# Arduino_Neptune.net
KiCad netlist of a schematic drawn in EAGLE
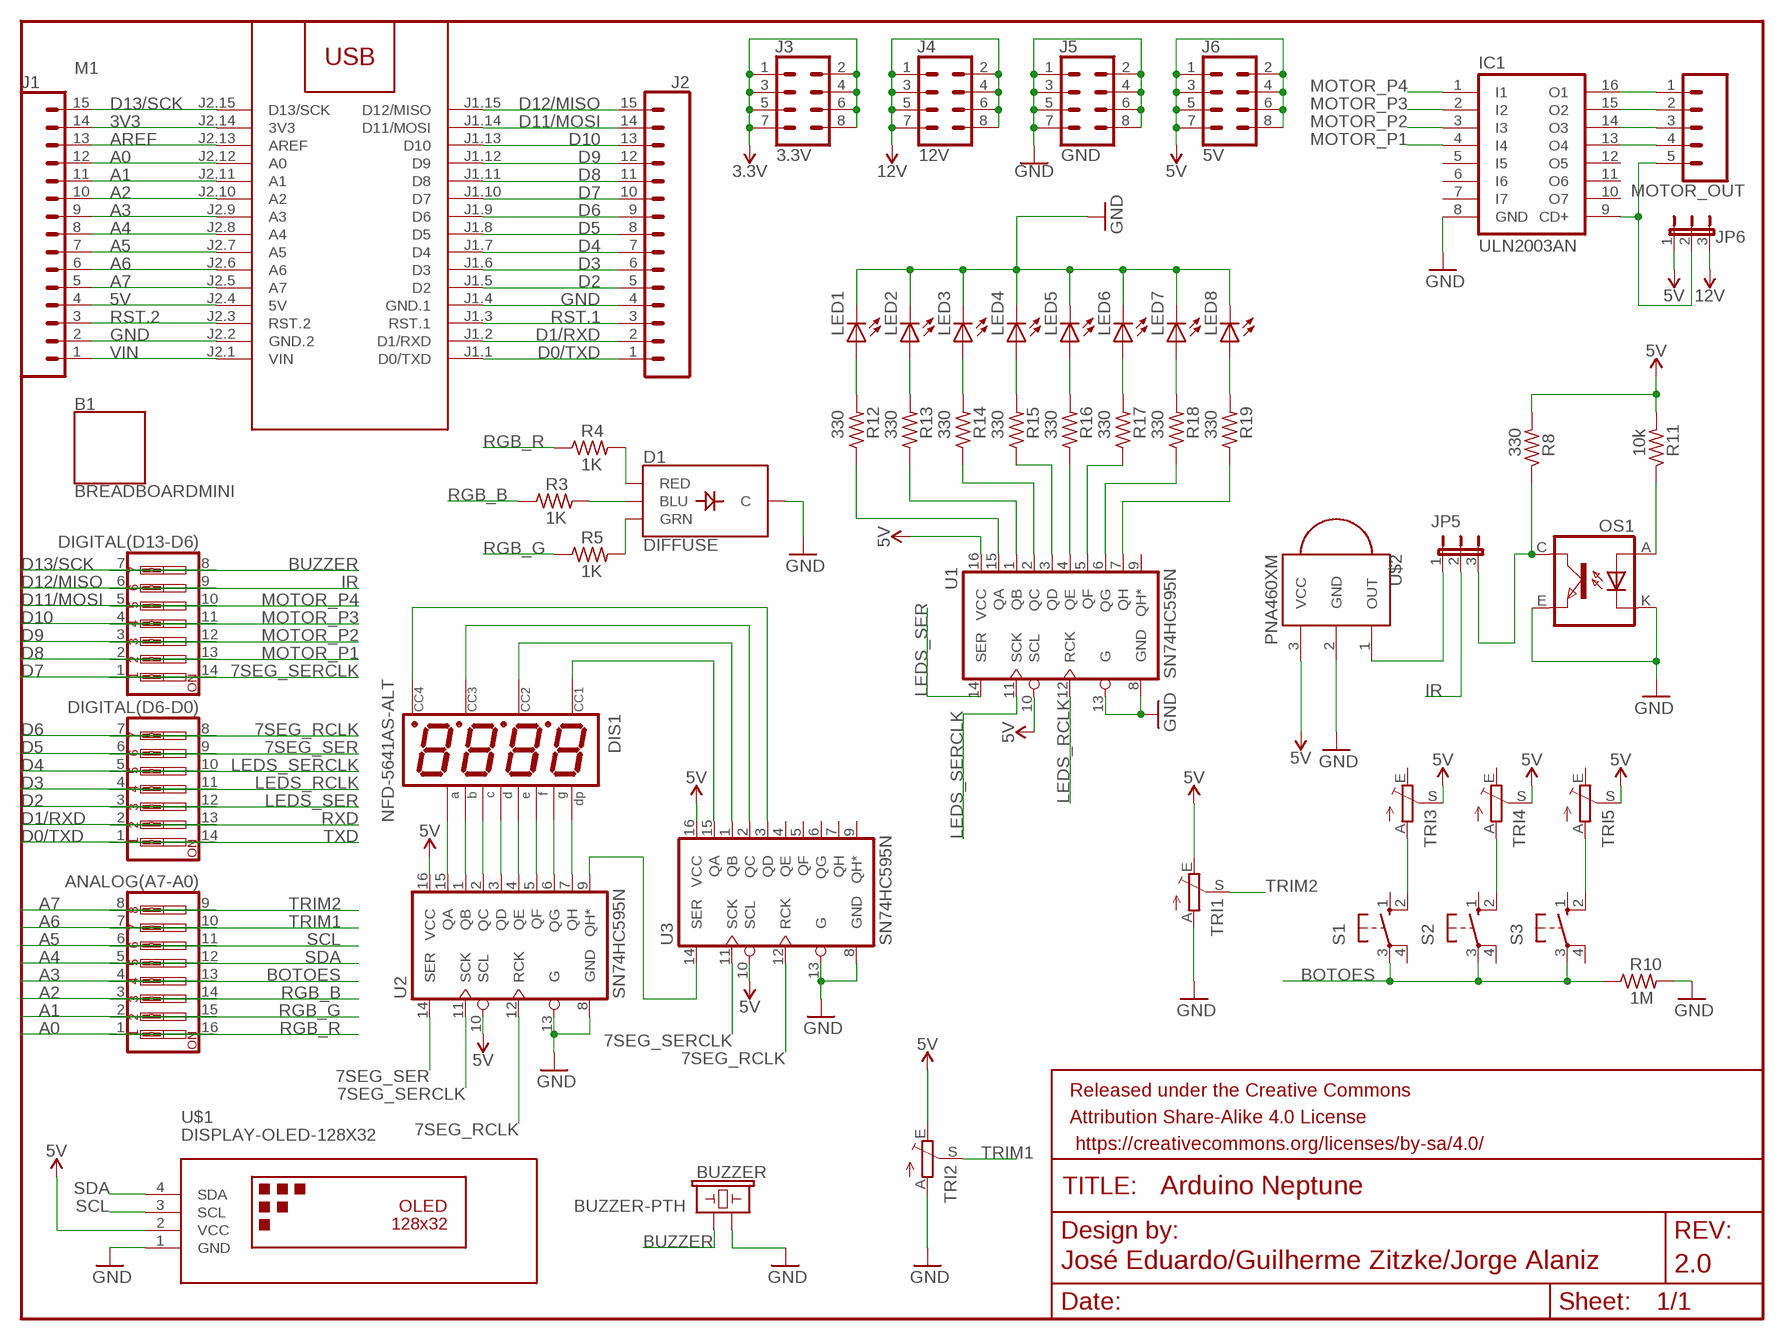
[diagram p0: schematic, sheet 1]

(export (version "E")
  (design (tool "Eeschema 10.0.6"))
  (components
    (comp (ref "ANALOG(A7-A0)")
      (value "SW_DIP-8")
      (footprint "eagle-import:EDG-08")
      (libsource (lib "eagle-import") (part "SW_DIP-8"))
    )
    (comp (ref "B1")
      (value "BREADBOARDMINI")
      (footprint "eagle-import:BREADBOARD-MINI")
      (libsource (lib "eagle-import") (part "BREADBOARDMINI"))
    )
    (comp (ref "BUZZER")
      (value "BUZZER-PTH")
      (footprint "eagle-import:BUZZER-12MM")
      (libsource (lib "eagle-import") (part "BUZZER-PTH"))
    )
    (comp (ref "D1")
      (value "DIFFUSE")
      (footprint "eagle-import:LED-RGB-THRU")
      (libsource (lib "eagle-import") (part "LED-RGB-CCDIFFUSE"))
    )
    (comp (ref "DIGITAL(D6-D0)")
      (value "SW_DIP-7")
      (footprint "eagle-import:EDG-07")
      (libsource (lib "eagle-import") (part "SW_DIP-7"))
    )
    (comp (ref "DIGITAL(D13-D6)")
      (value "SW_DIP-7")
      (footprint "eagle-import:EDG-07")
      (libsource (lib "eagle-import") (part "SW_DIP-7"))
    )
    (comp (ref "DIS1")
      (value "NFD-5641AS-ALT")
      (footprint "eagle-import:NFD-5641")
      (libsource (lib "eagle-import") (part "NFD-5641AS-ALT"))
    )
    (comp (ref "FRAME2")
      (value "FRAME-LETTER")
      (footprint "eagle-import:CREATIVE_COMMONS")
      (fields
        (field (name "DESIGNER") "José Eduardo/Guilherme Zitzke/Jorge Alaniz")
        (field (name "REV") "2.0")
      )
      (libsource (lib "eagle-import") (part "FRAME-LETTER"))
    )
    (comp (ref "IC1")
      (value "ULN2003AN")
      (footprint "eagle-import:DIL16")
      (libsource (lib "eagle-import") (part "ULN2003AN"))
    )
    (comp (ref "J1")
      (value "CONN_15LOCK_LONGPADS")
      (footprint "eagle-import:1X15_LOCK_LONGPADS")
      (libsource (lib "eagle-import") (part "CONN_15LOCK_LONGPADS"))
    )
    (comp (ref "J2")
      (value "CONN_15LOCK_LONGPADS")
      (footprint "eagle-import:1X15_LOCK_LONGPADS")
      (libsource (lib "eagle-import") (part "CONN_15LOCK_LONGPADS"))
    )
    (comp (ref "J3")
      (value "3.3V")
      (footprint "eagle-import:2X4")
      (libsource (lib "eagle-import") (part "CONN_04X2"))
    )
    (comp (ref "J4")
      (value "12V")
      (footprint "eagle-import:2X4")
      (libsource (lib "eagle-import") (part "CONN_04X2"))
    )
    (comp (ref "J5")
      (value "GND")
      (footprint "eagle-import:2X4")
      (libsource (lib "eagle-import") (part "CONN_04X2"))
    )
    (comp (ref "J6")
      (value "5V")
      (footprint "eagle-import:2X4")
      (libsource (lib "eagle-import") (part "CONN_04X2"))
    )
    (comp (ref "JP5")
      (value "JP2E")
      (footprint "eagle-import:JP2")
      (libsource (lib "eagle-import") (part "JP2E"))
    )
    (comp (ref "JP6")
      (value "JP2E")
      (footprint "eagle-import:JP2")
      (libsource (lib "eagle-import") (part "JP2E"))
    )
    (comp (ref "LED1")
      (value "LED5MM")
      (footprint "eagle-import:LED5MM")
      (libsource (lib "eagle-import") (part "LED5MM"))
    )
    (comp (ref "LED2")
      (value "LED5MM")
      (footprint "eagle-import:LED5MM")
      (libsource (lib "eagle-import") (part "LED5MM"))
    )
    (comp (ref "LED3")
      (value "LED5MM")
      (footprint "eagle-import:LED5MM")
      (libsource (lib "eagle-import") (part "LED5MM"))
    )
    (comp (ref "LED4")
      (value "LED5MM")
      (footprint "eagle-import:LED5MM")
      (libsource (lib "eagle-import") (part "LED5MM"))
    )
    (comp (ref "LED5")
      (value "LED5MM")
      (footprint "eagle-import:LED5MM")
      (libsource (lib "eagle-import") (part "LED5MM"))
    )
    (comp (ref "LED6")
      (value "LED5MM")
      (footprint "eagle-import:LED5MM")
      (libsource (lib "eagle-import") (part "LED5MM"))
    )
    (comp (ref "LED7")
      (value "LED5MM")
      (footprint "eagle-import:LED5MM")
      (libsource (lib "eagle-import") (part "LED5MM"))
    )
    (comp (ref "LED8")
      (value "LED5MM")
      (footprint "eagle-import:LED5MM")
      (libsource (lib "eagle-import") (part "LED5MM"))
    )
    (comp (ref "M1")
      (value "ARDUINO-NANO-3.0")
      (footprint "eagle-import:ARDUINO-NANO-3.0")
      (libsource (lib "eagle-import") (part "ARDUINO-NANO-3.0"))
    )
    (comp (ref "MOTOR_OUT")
      (value "CONN_05JST-VERT")
      (footprint "eagle-import:JST-5-PTH-VERT")
      (libsource (lib "eagle-import") (part "CONN_05JST-VERT"))
    )
    (comp (ref "OS1")
      (value "TCRT5000")
      (footprint "eagle-import:TCRT5000")
      (libsource (lib "eagle-import") (part "TCRT5000"))
    )
    (comp (ref "R3")
      (value "1K")
      (footprint "eagle-import:0204_7")
      (libsource (lib "eagle-import") (part "R-US_0204/7"))
    )
    (comp (ref "R4")
      (value "1K")
      (footprint "eagle-import:0204_7")
      (libsource (lib "eagle-import") (part "R-US_0204/7"))
    )
    (comp (ref "R5")
      (value "1K")
      (footprint "eagle-import:0204_7")
      (libsource (lib "eagle-import") (part "R-US_0204/7"))
    )
    (comp (ref "R8")
      (value "330")
      (footprint "eagle-import:0204_7")
      (libsource (lib "eagle-import") (part "R-US_0204/7"))
    )
    (comp (ref "R10")
      (value "1M")
      (footprint "eagle-import:0204_7")
      (libsource (lib "eagle-import") (part "R-US_0204/7"))
    )
    (comp (ref "R11")
      (value "10k")
      (footprint "eagle-import:0204_7")
      (libsource (lib "eagle-import") (part "R-US_0204/7"))
    )
    (comp (ref "R12")
      (value "330")
      (footprint "eagle-import:0204_7")
      (libsource (lib "eagle-import") (part "R-US_0204/7"))
    )
    (comp (ref "R13")
      (value "330")
      (footprint "eagle-import:0204_7")
      (libsource (lib "eagle-import") (part "R-US_0204/7"))
    )
    (comp (ref "R14")
      (value "330")
      (footprint "eagle-import:0204_7")
      (libsource (lib "eagle-import") (part "R-US_0204/7"))
    )
    (comp (ref "R15")
      (value "330")
      (footprint "eagle-import:0204_7")
      (libsource (lib "eagle-import") (part "R-US_0204/7"))
    )
    (comp (ref "R16")
      (value "330")
      (footprint "eagle-import:0204_7")
      (libsource (lib "eagle-import") (part "R-US_0204/7"))
    )
    (comp (ref "R17")
      (value "330")
      (footprint "eagle-import:0204_7")
      (libsource (lib "eagle-import") (part "R-US_0204/7"))
    )
    (comp (ref "R18")
      (value "330")
      (footprint "eagle-import:0204_7")
      (libsource (lib "eagle-import") (part "R-US_0204/7"))
    )
    (comp (ref "R19")
      (value "330")
      (footprint "eagle-import:0204_7")
      (libsource (lib "eagle-import") (part "R-US_0204/7"))
    )
    (comp (ref "S1")
      (value "40-XX")
      (footprint "eagle-import:B3F-40XX")
      (fields (field (name "MF") "OMRON COMPONENTS USA") (field (name "MPN") "B3F-4000"))
      (libsource (lib "eagle-import") (part "40-XX"))
    )
    (comp (ref "S2")
      (value "40-XX")
      (footprint "eagle-import:B3F-40XX")
      (fields (field (name "MF") "OMRON COMPONENTS USA") (field (name "MPN") "B3F-4000"))
      (libsource (lib "eagle-import") (part "40-XX"))
    )
    (comp (ref "S3")
      (value "40-XX")
      (footprint "eagle-import:B3F-40XX")
      (fields (field (name "MF") "OMRON COMPONENTS USA") (field (name "MPN") "B3F-4000"))
      (libsource (lib "eagle-import") (part "40-XX"))
    )
    (comp (ref "TRI1")
      (value "TRIM_EU-B64Y")
      (footprint "eagle-import:B64Y")
      (libsource (lib "eagle-import") (part "TRIM_EU-B64Y"))
    )
    (comp (ref "TRI2")
      (value "TRIM_EU-B64Y")
      (footprint "eagle-import:B64Y")
      (libsource (lib "eagle-import") (part "TRIM_EU-B64Y"))
    )
    (comp (ref "TRI3")
      (value "TRIM_EU-B64Y")
      (footprint "eagle-import:B64Y")
      (libsource (lib "eagle-import") (part "TRIM_EU-B64Y"))
    )
    (comp (ref "TRI4")
      (value "TRIM_EU-B64Y")
      (footprint "eagle-import:B64Y")
      (libsource (lib "eagle-import") (part "TRIM_EU-B64Y"))
    )
    (comp (ref "TRI5")
      (value "TRIM_EU-B64Y")
      (footprint "eagle-import:B64Y")
      (libsource (lib "eagle-import") (part "TRIM_EU-B64Y"))
    )
    (comp (ref "U$1")
      (value "DISPLAY-OLED-128X32")
      (footprint "eagle-import:DISPLAY-OLED-128X32")
      (libsource (lib "eagle-import") (part "DISPLAY-OLED-128X32"))
    )
    (comp (ref "U$2")
      (value "PNA460XM")
      (footprint "eagle-import:PNA460XM")
      (libsource (lib "eagle-import") (part "PNA460XM"))
    )
    (comp (ref "U1")
      (value "SN74HC595N")
      (footprint "eagle-import:DIP16")
      (libsource (lib "eagle-import") (part "74595NHC"))
    )
    (comp (ref "U2")
      (value "SN74HC595N")
      (footprint "eagle-import:DIP16")
      (libsource (lib "eagle-import") (part "74595NHC"))
    )
    (comp (ref "U3")
      (value "SN74HC595N")
      (footprint "eagle-import:DIP16")
      (libsource (lib "eagle-import") (part "74595NHC"))
    )
  )
  (nets
    (net (code "1") (name "/3V3") (class "Default")
      (node (ref "J1") (pin "14") (pinfunction "14_14") (pintype "passive"))
      (node (ref "M1") (pin "J2.14") (pinfunction "3V3_J2.14") (pintype "power_in"))
    )
    (net (code "2") (name "/7SEG_RCLK") (class "Default")
      (node (ref "DIGITAL(D6-D0)") (pin "7") (pinfunction "7_7") (pintype "passive"))
      (node (ref "U2") (pin "12") (pinfunction "RCK_12") (pintype "input"))
      (node (ref "U3") (pin "12") (pinfunction "RCK_12") (pintype "input"))
    )
    (net (code "3") (name "/7SEG_SER") (class "Default")
      (node (ref "DIGITAL(D6-D0)") (pin "6") (pinfunction "6_6") (pintype "passive"))
      (node (ref "U2") (pin "14") (pinfunction "SER_14") (pintype "input"))
    )
    (net (code "4") (name "/7SEG_SERCLK") (class "Default")
      (node (ref "DIGITAL(D13-D6)") (pin "1") (pinfunction "1_1") (pintype "passive"))
      (node (ref "U2") (pin "11") (pinfunction "SCK_11") (pintype "input"))
      (node (ref "U3") (pin "11") (pinfunction "SCK_11") (pintype "input"))
    )
    (net (code "5") (name "/A0") (class "Default")
      (node (ref "ANALOG(A7-A0)") (pin "16") (pinfunction "16_16") (pintype "passive"))
      (node (ref "J1") (pin "12") (pinfunction "12_12") (pintype "passive"))
      (node (ref "M1") (pin "J2.12") (pinfunction "A0_J2.12") (pintype "bidirectional"))
    )
    (net (code "6") (name "/A1") (class "Default")
      (node (ref "ANALOG(A7-A0)") (pin "15") (pinfunction "15_15") (pintype "passive"))
      (node (ref "J1") (pin "11") (pinfunction "11_11") (pintype "passive"))
      (node (ref "M1") (pin "J2.11") (pinfunction "A1_J2.11") (pintype "bidirectional"))
    )
    (net (code "7") (name "/A2") (class "Default")
      (node (ref "ANALOG(A7-A0)") (pin "14") (pinfunction "14_14") (pintype "passive"))
      (node (ref "J1") (pin "10") (pinfunction "10_10") (pintype "passive"))
      (node (ref "M1") (pin "J2.10") (pinfunction "A2_J2.10") (pintype "bidirectional"))
    )
    (net (code "8") (name "/A3") (class "Default")
      (node (ref "ANALOG(A7-A0)") (pin "13") (pinfunction "13_13") (pintype "passive"))
      (node (ref "J1") (pin "9") (pinfunction "9_9") (pintype "passive"))
      (node (ref "M1") (pin "J2.9") (pinfunction "A3_J2.9") (pintype "bidirectional"))
    )
    (net (code "9") (name "/A4") (class "Default")
      (node (ref "ANALOG(A7-A0)") (pin "12") (pinfunction "12_12") (pintype "passive"))
      (node (ref "J1") (pin "8") (pinfunction "8_8") (pintype "passive"))
      (node (ref "M1") (pin "J2.8") (pinfunction "A4_J2.8") (pintype "bidirectional"))
    )
    (net (code "10") (name "/A5") (class "Default")
      (node (ref "ANALOG(A7-A0)") (pin "11") (pinfunction "11_11") (pintype "passive"))
      (node (ref "J1") (pin "7") (pinfunction "7_7") (pintype "passive"))
      (node (ref "M1") (pin "J2.7") (pinfunction "A5_J2.7") (pintype "bidirectional"))
    )
    (net (code "11") (name "/A6") (class "Default")
      (node (ref "ANALOG(A7-A0)") (pin "10") (pinfunction "10_10") (pintype "passive"))
      (node (ref "J1") (pin "6") (pinfunction "6_6") (pintype "passive"))
      (node (ref "M1") (pin "J2.6") (pinfunction "A6_J2.6") (pintype "bidirectional"))
    )
    (net (code "12") (name "/A7") (class "Default")
      (node (ref "ANALOG(A7-A0)") (pin "9") (pinfunction "9_9") (pintype "passive"))
      (node (ref "J1") (pin "5") (pinfunction "5_5") (pintype "passive"))
      (node (ref "M1") (pin "J2.5") (pinfunction "A7_J2.5") (pintype "bidirectional"))
    )
    (net (code "13") (name "/AREF") (class "Default")
      (node (ref "J1") (pin "13") (pinfunction "13_13") (pintype "passive"))
      (node (ref "M1") (pin "J2.13") (pinfunction "AREF_J2.13") (pintype "bidirectional"))
    )
    (net (code "14") (name "/BOTOES") (class "Default")
      (node (ref "ANALOG(A7-A0)") (pin "4") (pinfunction "4_4") (pintype "passive"))
      (node (ref "R10") (pin "1") (pinfunction "1_1") (pintype "passive"))
      (node (ref "S1") (pin "3") (pinfunction "P_3") (pintype "passive"))
      (node (ref "S2") (pin "3") (pinfunction "P_3") (pintype "passive"))
      (node (ref "S3") (pin "3") (pinfunction "P_3") (pintype "passive"))
    )
    (net (code "15") (name "/BUZZER") (class "Default")
      (node (ref "BUZZER") (pin "+") (pinfunction "1_+") (pintype "passive"))
      (node (ref "DIGITAL(D13-D6)") (pin "7") (pinfunction "7_7") (pintype "passive"))
    )
    (net (code "16") (name "/D0{slash}TXD") (class "Default")
      (node (ref "DIGITAL(D6-D0)") (pin "14") (pinfunction "14_14") (pintype "passive"))
      (node (ref "J2") (pin "1") (pinfunction "1_1") (pintype "passive"))
      (node (ref "M1") (pin "J1.1") (pinfunction "D0/TXD_J1.1") (pintype "bidirectional"))
    )
    (net (code "17") (name "/D1{slash}RXD") (class "Default")
      (node (ref "DIGITAL(D6-D0)") (pin "13") (pinfunction "13_13") (pintype "passive"))
      (node (ref "J2") (pin "2") (pinfunction "2_2") (pintype "passive"))
      (node (ref "M1") (pin "J1.2") (pinfunction "D1/RXD_J1.2") (pintype "bidirectional"))
    )
    (net (code "18") (name "/D2") (class "Default")
      (node (ref "DIGITAL(D6-D0)") (pin "12") (pinfunction "12_12") (pintype "passive"))
      (node (ref "J2") (pin "5") (pinfunction "5_5") (pintype "passive"))
      (node (ref "M1") (pin "J1.5") (pinfunction "D2_J1.5") (pintype "bidirectional"))
    )
    (net (code "19") (name "/D3") (class "Default")
      (node (ref "DIGITAL(D6-D0)") (pin "11") (pinfunction "11_11") (pintype "passive"))
      (node (ref "J2") (pin "6") (pinfunction "6_6") (pintype "passive"))
      (node (ref "M1") (pin "J1.6") (pinfunction "D3_J1.6") (pintype "bidirectional"))
    )
    (net (code "20") (name "/D4") (class "Default")
      (node (ref "DIGITAL(D6-D0)") (pin "10") (pinfunction "10_10") (pintype "passive"))
      (node (ref "J2") (pin "7") (pinfunction "7_7") (pintype "passive"))
      (node (ref "M1") (pin "J1.7") (pinfunction "D4_J1.7") (pintype "bidirectional"))
    )
    (net (code "21") (name "/D5") (class "Default")
      (node (ref "DIGITAL(D6-D0)") (pin "9") (pinfunction "9_9") (pintype "passive"))
      (node (ref "J2") (pin "8") (pinfunction "8_8") (pintype "passive"))
      (node (ref "M1") (pin "J1.8") (pinfunction "D5_J1.8") (pintype "bidirectional"))
    )
    (net (code "22") (name "/D6") (class "Default")
      (node (ref "DIGITAL(D6-D0)") (pin "8") (pinfunction "8_8") (pintype "passive"))
      (node (ref "J2") (pin "9") (pinfunction "9_9") (pintype "passive"))
      (node (ref "M1") (pin "J1.9") (pinfunction "D6_J1.9") (pintype "bidirectional"))
    )
    (net (code "23") (name "/D7") (class "Default")
      (node (ref "DIGITAL(D13-D6)") (pin "14") (pinfunction "14_14") (pintype "passive"))
      (node (ref "J2") (pin "10") (pinfunction "10_10") (pintype "passive"))
      (node (ref "M1") (pin "J1.10") (pinfunction "D7_J1.10") (pintype "bidirectional"))
    )
    (net (code "24") (name "/D8") (class "Default")
      (node (ref "DIGITAL(D13-D6)") (pin "13") (pinfunction "13_13") (pintype "passive"))
      (node (ref "J2") (pin "11") (pinfunction "11_11") (pintype "passive"))
      (node (ref "M1") (pin "J1.11") (pinfunction "D8_J1.11") (pintype "bidirectional"))
    )
    (net (code "25") (name "/D9") (class "Default")
      (node (ref "DIGITAL(D13-D6)") (pin "12") (pinfunction "12_12") (pintype "passive"))
      (node (ref "J2") (pin "12") (pinfunction "12_12") (pintype "passive"))
      (node (ref "M1") (pin "J1.12") (pinfunction "D9_J1.12") (pintype "bidirectional"))
    )
    (net (code "26") (name "/D10") (class "Default")
      (node (ref "DIGITAL(D13-D6)") (pin "11") (pinfunction "11_11") (pintype "passive"))
      (node (ref "J2") (pin "13") (pinfunction "13_13") (pintype "passive"))
      (node (ref "M1") (pin "J1.13") (pinfunction "D10_J1.13") (pintype "bidirectional"))
    )
    (net (code "27") (name "/D11{slash}MOSI") (class "Default")
      (node (ref "DIGITAL(D13-D6)") (pin "10") (pinfunction "10_10") (pintype "passive"))
      (node (ref "J2") (pin "14") (pinfunction "14_14") (pintype "passive"))
      (node (ref "M1") (pin "J1.14") (pinfunction "D11/MOSI_J1.14") (pintype "bidirectional"))
    )
    (net (code "28") (name "/D12{slash}MISO") (class "Default")
      (node (ref "DIGITAL(D13-D6)") (pin "9") (pinfunction "9_9") (pintype "passive"))
      (node (ref "J2") (pin "15") (pinfunction "15_15") (pintype "passive"))
      (node (ref "M1") (pin "J1.15") (pinfunction "D12/MISO_J1.15") (pintype "bidirectional"))
    )
    (net (code "29") (name "/D13{slash}SCK") (class "Default")
      (node (ref "DIGITAL(D13-D6)") (pin "8") (pinfunction "8_8") (pintype "passive"))
      (node (ref "J1") (pin "15") (pinfunction "15_15") (pintype "passive"))
      (node (ref "M1") (pin "J2.15") (pinfunction "D13/SCK_J2.15") (pintype "bidirectional"))
    )
    (net (code "30") (name "/IR") (class "Default")
      (node (ref "DIGITAL(D13-D6)") (pin "6") (pinfunction "6_6") (pintype "passive"))
      (node (ref "JP5") (pin "2") (pinfunction "2_2") (pintype "passive"))
    )
    (net (code "31") (name "/LEDS_RCLK") (class "Default")
      (node (ref "DIGITAL(D6-D0)") (pin "4") (pinfunction "4_4") (pintype "passive"))
      (node (ref "U1") (pin "12") (pinfunction "RCK_12") (pintype "input"))
    )
    (net (code "32") (name "/LEDS_SER") (class "Default")
      (node (ref "DIGITAL(D6-D0)") (pin "3") (pinfunction "3_3") (pintype "passive"))
      (node (ref "U1") (pin "14") (pinfunction "SER_14") (pintype "input"))
    )
    (net (code "33") (name "/LEDS_SERCLK") (class "Default")
      (node (ref "DIGITAL(D6-D0)") (pin "5") (pinfunction "5_5") (pintype "passive"))
      (node (ref "U1") (pin "11") (pinfunction "SCK_11") (pintype "input"))
    )
    (net (code "34") (name "/MOTOR_P1") (class "Default")
      (node (ref "DIGITAL(D13-D6)") (pin "2") (pinfunction "2_2") (pintype "passive"))
      (node (ref "IC1") (pin "4") (pinfunction "I4_4") (pintype "input"))
    )
    (net (code "35") (name "/MOTOR_P2") (class "Default")
      (node (ref "DIGITAL(D13-D6)") (pin "3") (pinfunction "3_3") (pintype "passive"))
      (node (ref "IC1") (pin "3") (pinfunction "I3_3") (pintype "input"))
    )
    (net (code "36") (name "/MOTOR_P3") (class "Default")
      (node (ref "DIGITAL(D13-D6)") (pin "4") (pinfunction "4_4") (pintype "passive"))
      (node (ref "IC1") (pin "2") (pinfunction "I2_2") (pintype "input"))
    )
    (net (code "37") (name "/MOTOR_P4") (class "Default")
      (node (ref "DIGITAL(D13-D6)") (pin "5") (pinfunction "5_5") (pintype "passive"))
      (node (ref "IC1") (pin "1") (pinfunction "I1_1") (pintype "input"))
    )
    (net (code "38") (name "/RGB_B") (class "Default")
      (node (ref "ANALOG(A7-A0)") (pin "3") (pinfunction "3_3") (pintype "passive"))
      (node (ref "R3") (pin "1") (pinfunction "1_1") (pintype "passive"))
    )
    (net (code "39") (name "/RGB_G") (class "Default")
      (node (ref "ANALOG(A7-A0)") (pin "2") (pinfunction "2_2") (pintype "passive"))
      (node (ref "R5") (pin "1") (pinfunction "1_1") (pintype "passive"))
    )
    (net (code "40") (name "/RGB_R") (class "Default")
      (node (ref "ANALOG(A7-A0)") (pin "1") (pinfunction "1_1") (pintype "passive"))
      (node (ref "R4") (pin "1") (pinfunction "1_1") (pintype "passive"))
    )
    (net (code "41") (name "/RST.1") (class "Default")
      (node (ref "J2") (pin "3") (pinfunction "3_3") (pintype "passive"))
      (node (ref "M1") (pin "J1.3") (pinfunction "RST.1_J1.3") (pintype "bidirectional"))
    )
    (net (code "42") (name "/RST.2") (class "Default")
      (node (ref "J1") (pin "3") (pinfunction "3_3") (pintype "passive"))
      (node (ref "M1") (pin "J2.3") (pinfunction "RST.2_J2.3") (pintype "bidirectional"))
    )
    (net (code "43") (name "/RXD") (class "Default")
      (node (ref "DIGITAL(D6-D0)") (pin "2") (pinfunction "2_2") (pintype "passive"))
    )
    (net (code "44") (name "/SCL") (class "Default")
      (node (ref "ANALOG(A7-A0)") (pin "6") (pinfunction "6_6") (pintype "passive"))
      (node (ref "U$1") (pin "3") (pinfunction "SCL_3") (pintype "bidirectional"))
    )
    (net (code "45") (name "/SDA") (class "Default")
      (node (ref "ANALOG(A7-A0)") (pin "5") (pinfunction "5_5") (pintype "passive"))
      (node (ref "U$1") (pin "4") (pinfunction "SDA_4") (pintype "bidirectional"))
    )
    (net (code "46") (name "/TRIM1") (class "Default")
      (node (ref "ANALOG(A7-A0)") (pin "7") (pinfunction "7_7") (pintype "passive"))
      (node (ref "TRI2") (pin "S") (pinfunction "S_S") (pintype "passive"))
    )
    (net (code "47") (name "/TRIM2") (class "Default")
      (node (ref "ANALOG(A7-A0)") (pin "8") (pinfunction "8_8") (pintype "passive"))
      (node (ref "TRI1") (pin "S") (pinfunction "S_S") (pintype "passive"))
    )
    (net (code "48") (name "/TXD") (class "Default")
      (node (ref "DIGITAL(D6-D0)") (pin "1") (pinfunction "1_1") (pintype "passive"))
    )
    (net (code "49") (name "/VIN") (class "Default")
      (node (ref "J1") (pin "1") (pinfunction "1_1") (pintype "passive"))
      (node (ref "M1") (pin "J2.1") (pinfunction "VIN_J2.1") (pintype "power_in"))
    )
    (net (code "50") (name "3.3V") (class "Default")
      (node (ref "J3") (pin "1") (pinfunction "1_1") (pintype "passive"))
      (node (ref "J3") (pin "2") (pinfunction "2_2") (pintype "passive"))
      (node (ref "J3") (pin "3") (pinfunction "3_3") (pintype "passive"))
      (node (ref "J3") (pin "4") (pinfunction "4_4") (pintype "passive"))
      (node (ref "J3") (pin "5") (pinfunction "5_5") (pintype "passive"))
      (node (ref "J3") (pin "6") (pinfunction "6_6") (pintype "passive"))
      (node (ref "J3") (pin "7") (pinfunction "7_7") (pintype "passive"))
      (node (ref "J3") (pin "8") (pinfunction "8_8") (pintype "passive"))
    )
    (net (code "51") (name "5V") (class "Default")
      (node (ref "J1") (pin "4") (pinfunction "4_4") (pintype "passive"))
      (node (ref "J6") (pin "1") (pinfunction "1_1") (pintype "passive"))
      (node (ref "J6") (pin "2") (pinfunction "2_2") (pintype "passive"))
      (node (ref "J6") (pin "3") (pinfunction "3_3") (pintype "passive"))
      (node (ref "J6") (pin "4") (pinfunction "4_4") (pintype "passive"))
      (node (ref "J6") (pin "5") (pinfunction "5_5") (pintype "passive"))
      (node (ref "J6") (pin "6") (pinfunction "6_6") (pintype "passive"))
      (node (ref "J6") (pin "7") (pinfunction "7_7") (pintype "passive"))
      (node (ref "J6") (pin "8") (pinfunction "8_8") (pintype "passive"))
      (node (ref "JP6") (pin "1") (pinfunction "1_1") (pintype "passive"))
      (node (ref "M1") (pin "J2.4") (pinfunction "5V_J2.4") (pintype "power_in"))
      (node (ref "R11") (pin "2") (pinfunction "2_2") (pintype "passive"))
      (node (ref "R8") (pin "2") (pinfunction "2_2") (pintype "passive"))
      (node (ref "TRI1") (pin "E") (pinfunction "E_E") (pintype "passive"))
      (node (ref "TRI2") (pin "E") (pinfunction "E_E") (pintype "passive"))
      (node (ref "TRI3") (pin "S") (pinfunction "S_S") (pintype "passive"))
      (node (ref "TRI4") (pin "S") (pinfunction "S_S") (pintype "passive"))
      (node (ref "TRI5") (pin "S") (pinfunction "S_S") (pintype "passive"))
      (node (ref "U$1") (pin "2") (pinfunction "VCC_2") (pintype "power_in"))
      (node (ref "U$2") (pin "3") (pinfunction "VCC_3") (pintype "power_in"))
      (node (ref "U1") (pin "10") (pinfunction "SCL_10") (pintype "input"))
      (node (ref "U1") (pin "16") (pinfunction "VCC_16") (pintype "power_in"))
      (node (ref "U2") (pin "10") (pinfunction "SCL_10") (pintype "input"))
      (node (ref "U2") (pin "16") (pinfunction "VCC_16") (pintype "power_in"))
      (node (ref "U3") (pin "10") (pinfunction "SCL_10") (pintype "input"))
      (node (ref "U3") (pin "16") (pinfunction "VCC_16") (pintype "power_in"))
    )
    (net (code "52") (name "12V") (class "Default")
      (node (ref "J4") (pin "1") (pinfunction "1_1") (pintype "passive"))
      (node (ref "J4") (pin "2") (pinfunction "2_2") (pintype "passive"))
      (node (ref "J4") (pin "3") (pinfunction "3_3") (pintype "passive"))
      (node (ref "J4") (pin "4") (pinfunction "4_4") (pintype "passive"))
      (node (ref "J4") (pin "5") (pinfunction "5_5") (pintype "passive"))
      (node (ref "J4") (pin "6") (pinfunction "6_6") (pintype "passive"))
      (node (ref "J4") (pin "7") (pinfunction "7_7") (pintype "passive"))
      (node (ref "J4") (pin "8") (pinfunction "8_8") (pintype "passive"))
      (node (ref "JP6") (pin "3") (pinfunction "3_3") (pintype "passive"))
    )
    (net (code "53") (name "GND") (class "Default")
      (node (ref "BUZZER") (pin "-") (pinfunction "2_-") (pintype "passive"))
      (node (ref "D1") (pin "2") (pinfunction "C_2") (pintype "bidirectional"))
      (node (ref "IC1") (pin "8") (pinfunction "GND_8") (pintype "power_in"))
      (node (ref "J1") (pin "2") (pinfunction "2_2") (pintype "passive"))
      (node (ref "J2") (pin "4") (pinfunction "4_4") (pintype "passive"))
      (node (ref "J5") (pin "1") (pinfunction "1_1") (pintype "passive"))
      (node (ref "J5") (pin "2") (pinfunction "2_2") (pintype "passive"))
      (node (ref "J5") (pin "3") (pinfunction "3_3") (pintype "passive"))
      (node (ref "J5") (pin "4") (pinfunction "4_4") (pintype "passive"))
      (node (ref "J5") (pin "5") (pinfunction "5_5") (pintype "passive"))
      (node (ref "J5") (pin "6") (pinfunction "6_6") (pintype "passive"))
      (node (ref "J5") (pin "7") (pinfunction "7_7") (pintype "passive"))
      (node (ref "J5") (pin "8") (pinfunction "8_8") (pintype "passive"))
      (node (ref "LED1") (pin "K") (pinfunction "C_K") (pintype "passive"))
      (node (ref "LED2") (pin "K") (pinfunction "C_K") (pintype "passive"))
      (node (ref "LED3") (pin "K") (pinfunction "C_K") (pintype "passive"))
      (node (ref "LED4") (pin "K") (pinfunction "C_K") (pintype "passive"))
      (node (ref "LED5") (pin "K") (pinfunction "C_K") (pintype "passive"))
      (node (ref "LED6") (pin "K") (pinfunction "C_K") (pintype "passive"))
      (node (ref "LED7") (pin "K") (pinfunction "C_K") (pintype "passive"))
      (node (ref "LED8") (pin "K") (pinfunction "C_K") (pintype "passive"))
      (node (ref "M1") (pin "J1.4") (pinfunction "GND.1_J1.4") (pintype "power_in"))
      (node (ref "M1") (pin "J2.2") (pinfunction "GND.2_J2.2") (pintype "power_in"))
      (node (ref "OS1") (pin "E") (pinfunction "EMITTER_E") (pintype "passive"))
      (node (ref "OS1") (pin "K") (pinfunction "CATHODE_K") (pintype "passive"))
      (node (ref "R10") (pin "2") (pinfunction "2_2") (pintype "passive"))
      (node (ref "TRI1") (pin "A") (pinfunction "A_A") (pintype "passive"))
      (node (ref "TRI2") (pin "A") (pinfunction "A_A") (pintype "passive"))
      (node (ref "U$1") (pin "1") (pinfunction "GND_1") (pintype "power_in"))
      (node (ref "U$2") (pin "2") (pinfunction "GND_2") (pintype "power_in"))
      (node (ref "U1") (pin "13") (pinfunction "G_13") (pintype "input"))
      (node (ref "U1") (pin "8") (pinfunction "GND_8") (pintype "power_in"))
      (node (ref "U2") (pin "13") (pinfunction "G_13") (pintype "input"))
      (node (ref "U2") (pin "8") (pinfunction "GND_8") (pintype "power_in"))
      (node (ref "U3") (pin "13") (pinfunction "G_13") (pintype "input"))
      (node (ref "U3") (pin "8") (pinfunction "GND_8") (pintype "power_in"))
    )
    (net (code "54") (name "Net-(D1-BLU)") (class "Default")
      (node (ref "D1") (pin "4") (pinfunction "BLU_4") (pintype "bidirectional"))
      (node (ref "R3") (pin "2") (pinfunction "2_2") (pintype "passive"))
    )
    (net (code "55") (name "Net-(D1-GRN)") (class "Default")
      (node (ref "D1") (pin "3") (pinfunction "GRN_3") (pintype "bidirectional"))
      (node (ref "R5") (pin "2") (pinfunction "2_2") (pintype "passive"))
    )
    (net (code "56") (name "Net-(D1-RED)") (class "Default")
      (node (ref "D1") (pin "1") (pinfunction "RED_1") (pintype "bidirectional"))
      (node (ref "R4") (pin "2") (pinfunction "2_2") (pintype "passive"))
    )
    (net (code "57") (name "Net-(IC1-CD+)") (class "Default")
      (node (ref "IC1") (pin "9") (pinfunction "CD+_9") (pintype "passive"))
      (node (ref "JP6") (pin "2") (pinfunction "2_2") (pintype "passive"))
      (node (ref "MOTOR_OUT") (pin "5") (pinfunction "5_5") (pintype "passive"))
    )
    (net (code "58") (name "Net-(IC1-O1)") (class "Default")
      (node (ref "IC1") (pin "16") (pinfunction "O1_16") (pintype "open_collector"))
      (node (ref "MOTOR_OUT") (pin "1") (pinfunction "1_1") (pintype "passive"))
    )
    (net (code "59") (name "Net-(IC1-O2)") (class "Default")
      (node (ref "IC1") (pin "15") (pinfunction "O2_15") (pintype "open_collector"))
      (node (ref "MOTOR_OUT") (pin "2") (pinfunction "2_2") (pintype "passive"))
    )
    (net (code "60") (name "Net-(IC1-O3)") (class "Default")
      (node (ref "IC1") (pin "14") (pinfunction "O3_14") (pintype "open_collector"))
      (node (ref "MOTOR_OUT") (pin "3") (pinfunction "3_3") (pintype "passive"))
    )
    (net (code "61") (name "Net-(IC1-O4)") (class "Default")
      (node (ref "IC1") (pin "13") (pinfunction "O4_13") (pintype "open_collector"))
      (node (ref "MOTOR_OUT") (pin "4") (pinfunction "4_4") (pintype "passive"))
    )
    (net (code "62") (name "Net-(LED1-PadA)") (class "Default")
      (node (ref "LED1") (pin "A") (pinfunction "A_A") (pintype "passive"))
      (node (ref "R12") (pin "2") (pinfunction "2_2") (pintype "passive"))
    )
    (net (code "63") (name "Net-(LED2-PadA)") (class "Default")
      (node (ref "LED2") (pin "A") (pinfunction "A_A") (pintype "passive"))
      (node (ref "R13") (pin "2") (pinfunction "2_2") (pintype "passive"))
    )
    (net (code "64") (name "Net-(LED3-PadA)") (class "Default")
      (node (ref "LED3") (pin "A") (pinfunction "A_A") (pintype "passive"))
      (node (ref "R14") (pin "2") (pinfunction "2_2") (pintype "passive"))
    )
    (net (code "65") (name "Net-(LED4-PadA)") (class "Default")
      (node (ref "LED4") (pin "A") (pinfunction "A_A") (pintype "passive"))
      (node (ref "R15") (pin "2") (pinfunction "2_2") (pintype "passive"))
    )
    (net (code "66") (name "Net-(LED5-PadA)") (class "Default")
      (node (ref "LED5") (pin "A") (pinfunction "A_A") (pintype "passive"))
      (node (ref "R16") (pin "2") (pinfunction "2_2") (pintype "passive"))
    )
    (net (code "67") (name "Net-(LED6-PadA)") (class "Default")
      (node (ref "LED6") (pin "A") (pinfunction "A_A") (pintype "passive"))
      (node (ref "R17") (pin "2") (pinfunction "2_2") (pintype "passive"))
    )
    (net (code "68") (name "Net-(LED7-PadA)") (class "Default")
      (node (ref "LED7") (pin "A") (pinfunction "A_A") (pintype "passive"))
      (node (ref "R18") (pin "2") (pinfunction "2_2") (pintype "passive"))
    )
    (net (code "69") (name "Net-(LED8-PadA)") (class "Default")
      (node (ref "LED8") (pin "A") (pinfunction "A_A") (pintype "passive"))
      (node (ref "R19") (pin "2") (pinfunction "2_2") (pintype "passive"))
    )
    (net (code "70") (name "Net-(OS1-ANODE)") (class "Default")
      (node (ref "OS1") (pin "A") (pinfunction "ANODE_A") (pintype "passive"))
      (node (ref "R11") (pin "1") (pinfunction "1_1") (pintype "passive"))
    )
    (net (code "71") (name "Net-(OS1-COLLECTOR)") (class "Default")
      (node (ref "JP5") (pin "3") (pinfunction "3_3") (pintype "passive"))
      (node (ref "OS1") (pin "C") (pinfunction "COLLECTOR_C") (pintype "passive"))
      (node (ref "R8") (pin "1") (pinfunction "1_1") (pintype "passive"))
    )
    (net (code "72") (name "Net-(S1-S1)") (class "Default")
      (node (ref "S1") (pin "2") (pinfunction "S1_2") (pintype "passive"))
      (node (ref "TRI3") (pin "A") (pinfunction "A_A") (pintype "passive"))
    )
    (net (code "73") (name "Net-(S2-S1)") (class "Default")
      (node (ref "S2") (pin "2") (pinfunction "S1_2") (pintype "passive"))
      (node (ref "TRI4") (pin "A") (pinfunction "A_A") (pintype "passive"))
    )
    (net (code "74") (name "Net-(S3-S1)") (class "Default")
      (node (ref "S3") (pin "2") (pinfunction "S1_2") (pintype "passive"))
      (node (ref "TRI5") (pin "A") (pinfunction "A_A") (pintype "passive"))
    )
    (net (code "75") (name "Net-(U$2-OUT)") (class "Default")
      (node (ref "JP5") (pin "1") (pinfunction "1_1") (pintype "passive"))
      (node (ref "U$2") (pin "1") (pinfunction "OUT_1") (pintype "output"))
    )
    (net (code "76") (name "Net-(U1-QA)") (class "Default")
      (node (ref "R12") (pin "1") (pinfunction "1_1") (pintype "passive"))
      (node (ref "U1") (pin "15") (pinfunction "QA_15") (pintype "tri_state"))
    )
    (net (code "77") (name "Net-(U1-QB)") (class "Default")
      (node (ref "R13") (pin "1") (pinfunction "1_1") (pintype "passive"))
      (node (ref "U1") (pin "1") (pinfunction "QB_1") (pintype "tri_state"))
    )
    (net (code "78") (name "Net-(U1-QC)") (class "Default")
      (node (ref "R14") (pin "1") (pinfunction "1_1") (pintype "passive"))
      (node (ref "U1") (pin "2") (pinfunction "QC_2") (pintype "tri_state"))
    )
    (net (code "79") (name "Net-(U1-QD)") (class "Default")
      (node (ref "R15") (pin "1") (pinfunction "1_1") (pintype "passive"))
      (node (ref "U1") (pin "3") (pinfunction "QD_3") (pintype "tri_state"))
    )
    (net (code "80") (name "Net-(U1-QE)") (class "Default")
      (node (ref "R16") (pin "1") (pinfunction "1_1") (pintype "passive"))
      (node (ref "U1") (pin "4") (pinfunction "QE_4") (pintype "tri_state"))
    )
    (net (code "81") (name "Net-(U1-QF)") (class "Default")
      (node (ref "R17") (pin "1") (pinfunction "1_1") (pintype "passive"))
      (node (ref "U1") (pin "5") (pinfunction "QF_5") (pintype "tri_state"))
    )
    (net (code "82") (name "Net-(U1-QG)") (class "Default")
      (node (ref "R18") (pin "1") (pinfunction "1_1") (pintype "passive"))
      (node (ref "U1") (pin "6") (pinfunction "QG_6") (pintype "tri_state"))
    )
    (net (code "83") (name "Net-(U1-QH)") (class "Default")
      (node (ref "R19") (pin "1") (pinfunction "1_1") (pintype "passive"))
      (node (ref "U1") (pin "7") (pinfunction "QH_7") (pintype "tri_state"))
    )
    (net (code "84") (name "Net-(U2-QA)") (class "Default")
      (node (ref "DIS1") (pin "P$11") (pinfunction "P$11_P$11") (pintype "bidirectional"))
      (node (ref "U2") (pin "15") (pinfunction "QA_15") (pintype "tri_state"))
    )
    (net (code "85") (name "Net-(U2-QB)") (class "Default")
      (node (ref "DIS1") (pin "P$7") (pinfunction "P$7_P$7") (pintype "bidirectional"))
      (node (ref "U2") (pin "1") (pinfunction "QB_1") (pintype "tri_state"))
    )
    (net (code "86") (name "Net-(U2-QC)") (class "Default")
      (node (ref "DIS1") (pin "P$4") (pinfunction "P$4_P$4") (pintype "bidirectional"))
      (node (ref "U2") (pin "2") (pinfunction "QC_2") (pintype "tri_state"))
    )
    (net (code "87") (name "Net-(U2-QD)") (class "Default")
      (node (ref "DIS1") (pin "P$2") (pinfunction "P$2_P$2") (pintype "bidirectional"))
      (node (ref "U2") (pin "3") (pinfunction "QD_3") (pintype "tri_state"))
    )
    (net (code "88") (name "Net-(U2-QE)") (class "Default")
      (node (ref "DIS1") (pin "P$1") (pinfunction "P$1_P$1") (pintype "bidirectional"))
      (node (ref "U2") (pin "4") (pinfunction "QE_4") (pintype "tri_state"))
    )
    (net (code "89") (name "Net-(U2-QF)") (class "Default")
      (node (ref "DIS1") (pin "P$10") (pinfunction "P$10_P$10") (pintype "bidirectional"))
      (node (ref "U2") (pin "5") (pinfunction "QF_5") (pintype "tri_state"))
    )
    (net (code "90") (name "Net-(U2-QG)") (class "Default")
      (node (ref "DIS1") (pin "P$5") (pinfunction "P$5_P$5") (pintype "bidirectional"))
      (node (ref "U2") (pin "6") (pinfunction "QG_6") (pintype "tri_state"))
    )
    (net (code "91") (name "Net-(U2-QH)") (class "Default")
      (node (ref "DIS1") (pin "P$3") (pinfunction "P$3_P$3") (pintype "bidirectional"))
      (node (ref "U2") (pin "7") (pinfunction "QH_7") (pintype "tri_state"))
    )
    (net (code "92") (name "Net-(U2-QH*)") (class "Default")
      (node (ref "U2") (pin "9") (pinfunction "QH*_9") (pintype "tri_state"))
      (node (ref "U3") (pin "14") (pinfunction "SER_14") (pintype "input"))
    )
    (net (code "93") (name "Net-(U3-QA)") (class "Default")
      (node (ref "DIS1") (pin "P$12") (pinfunction "P$12_P$12") (pintype "bidirectional"))
      (node (ref "U3") (pin "15") (pinfunction "QA_15") (pintype "tri_state"))
    )
    (net (code "94") (name "Net-(U3-QB)") (class "Default")
      (node (ref "DIS1") (pin "P$9") (pinfunction "P$9_P$9") (pintype "bidirectional"))
      (node (ref "U3") (pin "1") (pinfunction "QB_1") (pintype "tri_state"))
    )
    (net (code "95") (name "Net-(U3-QC)") (class "Default")
      (node (ref "DIS1") (pin "P$8") (pinfunction "P$8_P$8") (pintype "bidirectional"))
      (node (ref "U3") (pin "2") (pinfunction "QC_2") (pintype "tri_state"))
    )
    (net (code "96") (name "Net-(U3-QD)") (class "Default")
      (node (ref "DIS1") (pin "P$6") (pinfunction "P$6_P$6") (pintype "bidirectional"))
      (node (ref "U3") (pin "3") (pinfunction "QD_3") (pintype "tri_state"))
    )
    (net (code "97") (name "unconnected-(IC1-I5-Pad5)") (class "Default")
      (node (ref "IC1") (pin "5") (pinfunction "I5_5") (pintype "input"))
    )
    (net (code "98") (name "unconnected-(IC1-I6-Pad6)") (class "Default")
      (node (ref "IC1") (pin "6") (pinfunction "I6_6") (pintype "input"))
    )
    (net (code "99") (name "unconnected-(IC1-I7-Pad7)") (class "Default")
      (node (ref "IC1") (pin "7") (pinfunction "I7_7") (pintype "input"))
    )
    (net (code "100") (name "unconnected-(IC1-O5-Pad12)") (class "Default")
      (node (ref "IC1") (pin "12") (pinfunction "O5_12") (pintype "open_collector"))
    )
    (net (code "101") (name "unconnected-(IC1-O6-Pad11)") (class "Default")
      (node (ref "IC1") (pin "11") (pinfunction "O6_11") (pintype "open_collector"))
    )
    (net (code "102") (name "unconnected-(IC1-O7-Pad10)") (class "Default")
      (node (ref "IC1") (pin "10") (pinfunction "O7_10") (pintype "open_collector"))
    )
    (net (code "103") (name "unconnected-(S1-P1-Pad4)") (class "Default")
      (node (ref "S1") (pin "4") (pinfunction "P1_4") (pintype "passive"))
    )
    (net (code "104") (name "unconnected-(S1-S-Pad1)") (class "Default")
      (node (ref "S1") (pin "1") (pinfunction "S_1") (pintype "passive"))
    )
    (net (code "105") (name "unconnected-(S2-P1-Pad4)") (class "Default")
      (node (ref "S2") (pin "4") (pinfunction "P1_4") (pintype "passive"))
    )
    (net (code "106") (name "unconnected-(S2-S-Pad1)") (class "Default")
      (node (ref "S2") (pin "1") (pinfunction "S_1") (pintype "passive"))
    )
    (net (code "107") (name "unconnected-(S3-P1-Pad4)") (class "Default")
      (node (ref "S3") (pin "4") (pinfunction "P1_4") (pintype "passive"))
    )
    (net (code "108") (name "unconnected-(S3-S-Pad1)") (class "Default")
      (node (ref "S3") (pin "1") (pinfunction "S_1") (pintype "passive"))
    )
    (net (code "109") (name "unconnected-(TRI3-PadE)") (class "Default")
      (node (ref "TRI3") (pin "E") (pinfunction "E_E") (pintype "passive"))
    )
    (net (code "110") (name "unconnected-(TRI4-PadE)") (class "Default")
      (node (ref "TRI4") (pin "E") (pinfunction "E_E") (pintype "passive"))
    )
    (net (code "111") (name "unconnected-(TRI5-PadE)") (class "Default")
      (node (ref "TRI5") (pin "E") (pinfunction "E_E") (pintype "passive"))
    )
    (net (code "112") (name "unconnected-(U1-QH*-Pad9)") (class "Default")
      (node (ref "U1") (pin "9") (pinfunction "QH*_9") (pintype "tri_state"))
    )
    (net (code "113") (name "unconnected-(U3-QE-Pad4)") (class "Default")
      (node (ref "U3") (pin "4") (pinfunction "QE_4") (pintype "tri_state"))
    )
    (net (code "114") (name "unconnected-(U3-QF-Pad5)") (class "Default")
      (node (ref "U3") (pin "5") (pinfunction "QF_5") (pintype "tri_state"))
    )
    (net (code "115") (name "unconnected-(U3-QG-Pad6)") (class "Default")
      (node (ref "U3") (pin "6") (pinfunction "QG_6") (pintype "tri_state"))
    )
    (net (code "116") (name "unconnected-(U3-QH*-Pad9)") (class "Default")
      (node (ref "U3") (pin "9") (pinfunction "QH*_9") (pintype "tri_state"))
    )
    (net (code "117") (name "unconnected-(U3-QH-Pad7)") (class "Default")
      (node (ref "U3") (pin "7") (pinfunction "QH_7") (pintype "tri_state"))
    )
  )
)
